# XIAO_ESP32C3_Adapter_board_copy.net
KiCad netlist of a schematic drawn in EasyEDA Pro
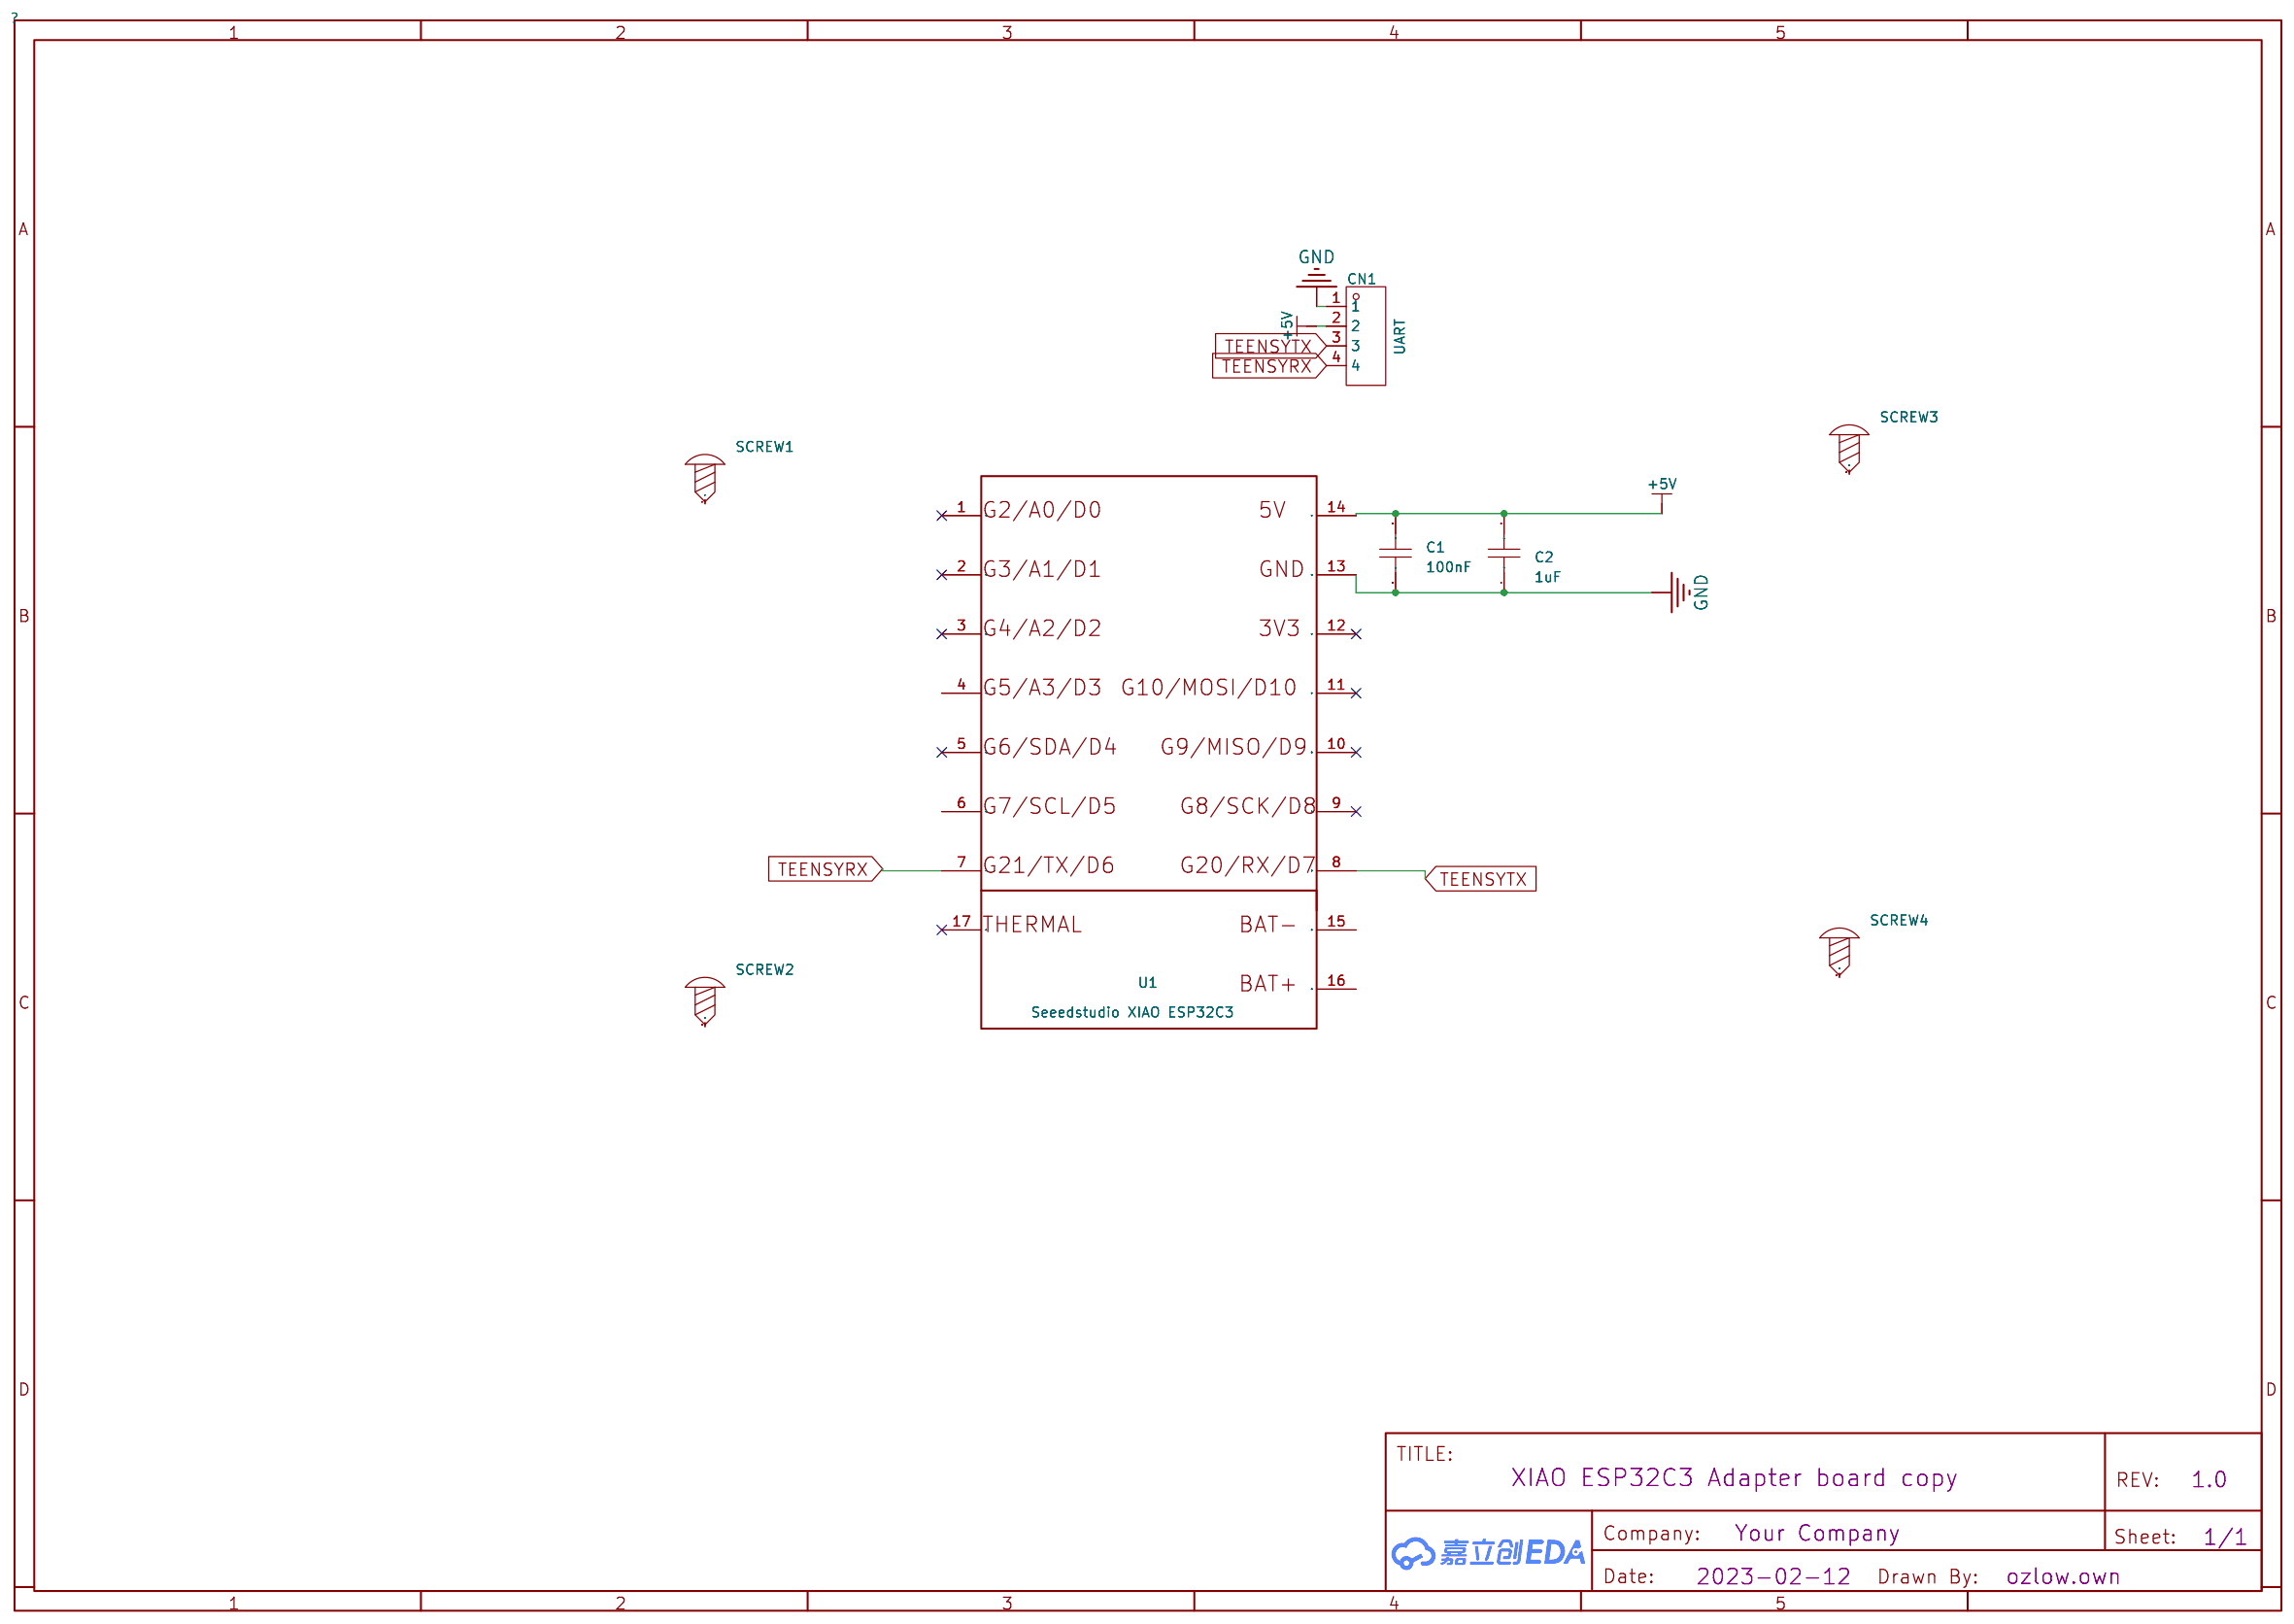
[diagram p0: schematic sheet]

(export (version "E")
  (design (tool "Eeschema 10.0.6"))
  (components
    (comp (ref "C1")
      (value "100nF")
      (footprint "easyedapro:C0201")
      (description "Capacitance:100nF Tolerance:±10% Tolerance:±10% Voltage Rating:16V Temperature Coefficient:-")
      (fields (field (name "Manufacturer Part") "C0201B104K016T") (field (name "Manufacturer") "IHHEC(禾伸堂)"))
      (libsource (lib "easyedapro") (part "CAP"))
    )
    (comp (ref "C2")
      (value "1uF")
      (footprint "easyedapro:C0201")
      (description "Capacitance:1uF Tolerance:±10% Tolerance:±10% Voltage Rating:6.3V Temperature Coefficient:X5R")
      (fields
        (field (name "Manufacturer Part") "CC0201KRX5R5BB105")
        (field (name "Manufacturer") "YAGEO(国巨)")
      )
      (libsource (lib "easyedapro") (part "CAP"))
    )
    (comp (ref "CN1")
      (value "UART")
      (footprint "easyedapro:CONN-TH_4P-P2.50_4PIN")
      (fields (field (name "Manufacturer Part") "XH2.54-4") (field (name "Manufacturer") "Megastar(兆星)"))
      (libsource (lib "easyedapro") (part "ZX-XH2.54-4PZZ"))
    )
    (comp (ref "SCREW1")
      (value "~")
      (footprint "easyedapro:Screw-Hole-M2")
      (libsource (lib "easyedapro") (part "Screw-Hole"))
    )
    (comp (ref "SCREW2")
      (value "~")
      (footprint "easyedapro:Screw-Hole-M2")
      (libsource (lib "easyedapro") (part "Screw-Hole"))
    )
    (comp (ref "SCREW3")
      (value "~")
      (footprint "easyedapro:Screw-Hole-M2")
      (libsource (lib "easyedapro") (part "Screw-Hole"))
    )
    (comp (ref "SCREW4")
      (value "~")
      (footprint "easyedapro:Screw-Hole-M2")
      (libsource (lib "easyedapro") (part "Screw-Hole"))
    )
    (comp (ref "U1")
      (value "Seeedstudio XIAO ESP32C3")
      (fields
        (field (name "Manufacturer Part") "113991054")
        (field (name "Manufacturer") "Seeedstudio")
        (field (name "Contributor") "ozlow.own")
      )
      (libsource (lib "easyedapro") (part "Seeedstudio XIAO ESP32C3"))
    )
  )
  (nets
    (net (code "1") (name "+5V") (class "Default")
      (node (ref "C1") (pin "2") (pinfunction "2_2") (pintype "input"))
      (node (ref "C2") (pin "2") (pinfunction "2_2") (pintype "input"))
      (node (ref "CN1") (pin "2") (pinfunction "2_2") (pintype "unspecified"))
      (node (ref "U1") (pin "14") (pinfunction "14_14") (pintype "unspecified"))
    )
    (net (code "2") (name "GND") (class "Default")
      (node (ref "C1") (pin "1") (pinfunction "1_1") (pintype "input"))
      (node (ref "C2") (pin "1") (pinfunction "1_1") (pintype "input"))
      (node (ref "CN1") (pin "1") (pinfunction "1_1") (pintype "unspecified"))
      (node (ref "U1") (pin "13") (pinfunction "13_13") (pintype "unspecified"))
    )
    (net (code "3") (name "TEENSYRX") (class "Default")
      (node (ref "CN1") (pin "4") (pinfunction "4_4") (pintype "unspecified"))
      (node (ref "U1") (pin "7") (pinfunction "7_7") (pintype "unspecified"))
    )
    (net (code "4") (name "TEENSYTX") (class "Default")
      (node (ref "CN1") (pin "3") (pinfunction "3_3") (pintype "unspecified"))
      (node (ref "U1") (pin "8") (pinfunction "8_8") (pintype "unspecified"))
    )
    (net (code "5") (name "unconnected-(SCREW1-Pad1)") (class "Default")
      (node (ref "SCREW1") (pin "1") (pinfunction "1_1") (pintype "input"))
    )
    (net (code "6") (name "unconnected-(SCREW2-Pad1)") (class "Default")
      (node (ref "SCREW2") (pin "1") (pinfunction "1_1") (pintype "input"))
    )
    (net (code "7") (name "unconnected-(SCREW3-Pad1)") (class "Default")
      (node (ref "SCREW3") (pin "1") (pinfunction "1_1") (pintype "input"))
    )
    (net (code "8") (name "unconnected-(SCREW4-Pad1)") (class "Default")
      (node (ref "SCREW4") (pin "1") (pinfunction "1_1") (pintype "input"))
    )
    (net (code "9") (name "unconnected-(U1-Pad1)") (class "Default")
      (node (ref "U1") (pin "1") (pinfunction "1_1") (pintype "unspecified+no_connect"))
    )
    (net (code "10") (name "unconnected-(U1-Pad2)") (class "Default")
      (node (ref "U1") (pin "2") (pinfunction "2_2") (pintype "unspecified+no_connect"))
    )
    (net (code "11") (name "unconnected-(U1-Pad3)") (class "Default")
      (node (ref "U1") (pin "3") (pinfunction "3_3") (pintype "unspecified+no_connect"))
    )
    (net (code "12") (name "unconnected-(U1-Pad4)") (class "Default")
      (node (ref "U1") (pin "4") (pinfunction "4_4") (pintype "unspecified"))
    )
    (net (code "13") (name "unconnected-(U1-Pad5)") (class "Default")
      (node (ref "U1") (pin "5") (pinfunction "5_5") (pintype "unspecified+no_connect"))
    )
    (net (code "14") (name "unconnected-(U1-Pad6)") (class "Default")
      (node (ref "U1") (pin "6") (pinfunction "6_6") (pintype "unspecified"))
    )
    (net (code "15") (name "unconnected-(U1-Pad9)") (class "Default")
      (node (ref "U1") (pin "9") (pinfunction "9_9") (pintype "unspecified+no_connect"))
    )
    (net (code "16") (name "unconnected-(U1-Pad10)") (class "Default")
      (node (ref "U1") (pin "10") (pinfunction "10_10") (pintype "unspecified+no_connect"))
    )
    (net (code "17") (name "unconnected-(U1-Pad11)") (class "Default")
      (node (ref "U1") (pin "11") (pinfunction "11_11") (pintype "unspecified+no_connect"))
    )
    (net (code "18") (name "unconnected-(U1-Pad12)") (class "Default")
      (node (ref "U1") (pin "12") (pinfunction "12_12") (pintype "unspecified+no_connect"))
    )
    (net (code "19") (name "unconnected-(U1-Pad15)") (class "Default")
      (node (ref "U1") (pin "15") (pinfunction "15_15") (pintype "unspecified"))
    )
    (net (code "20") (name "unconnected-(U1-Pad16)") (class "Default")
      (node (ref "U1") (pin "16") (pinfunction "16_16") (pintype "unspecified"))
    )
    (net (code "21") (name "unconnected-(U1-Pad17)") (class "Default")
      (node (ref "U1") (pin "17") (pinfunction "17_17") (pintype "unspecified+no_connect"))
    )
  )
)
